# Inductive_displacement_sensor.net
KiCad netlist of a schematic drawn in EasyEDA Pro
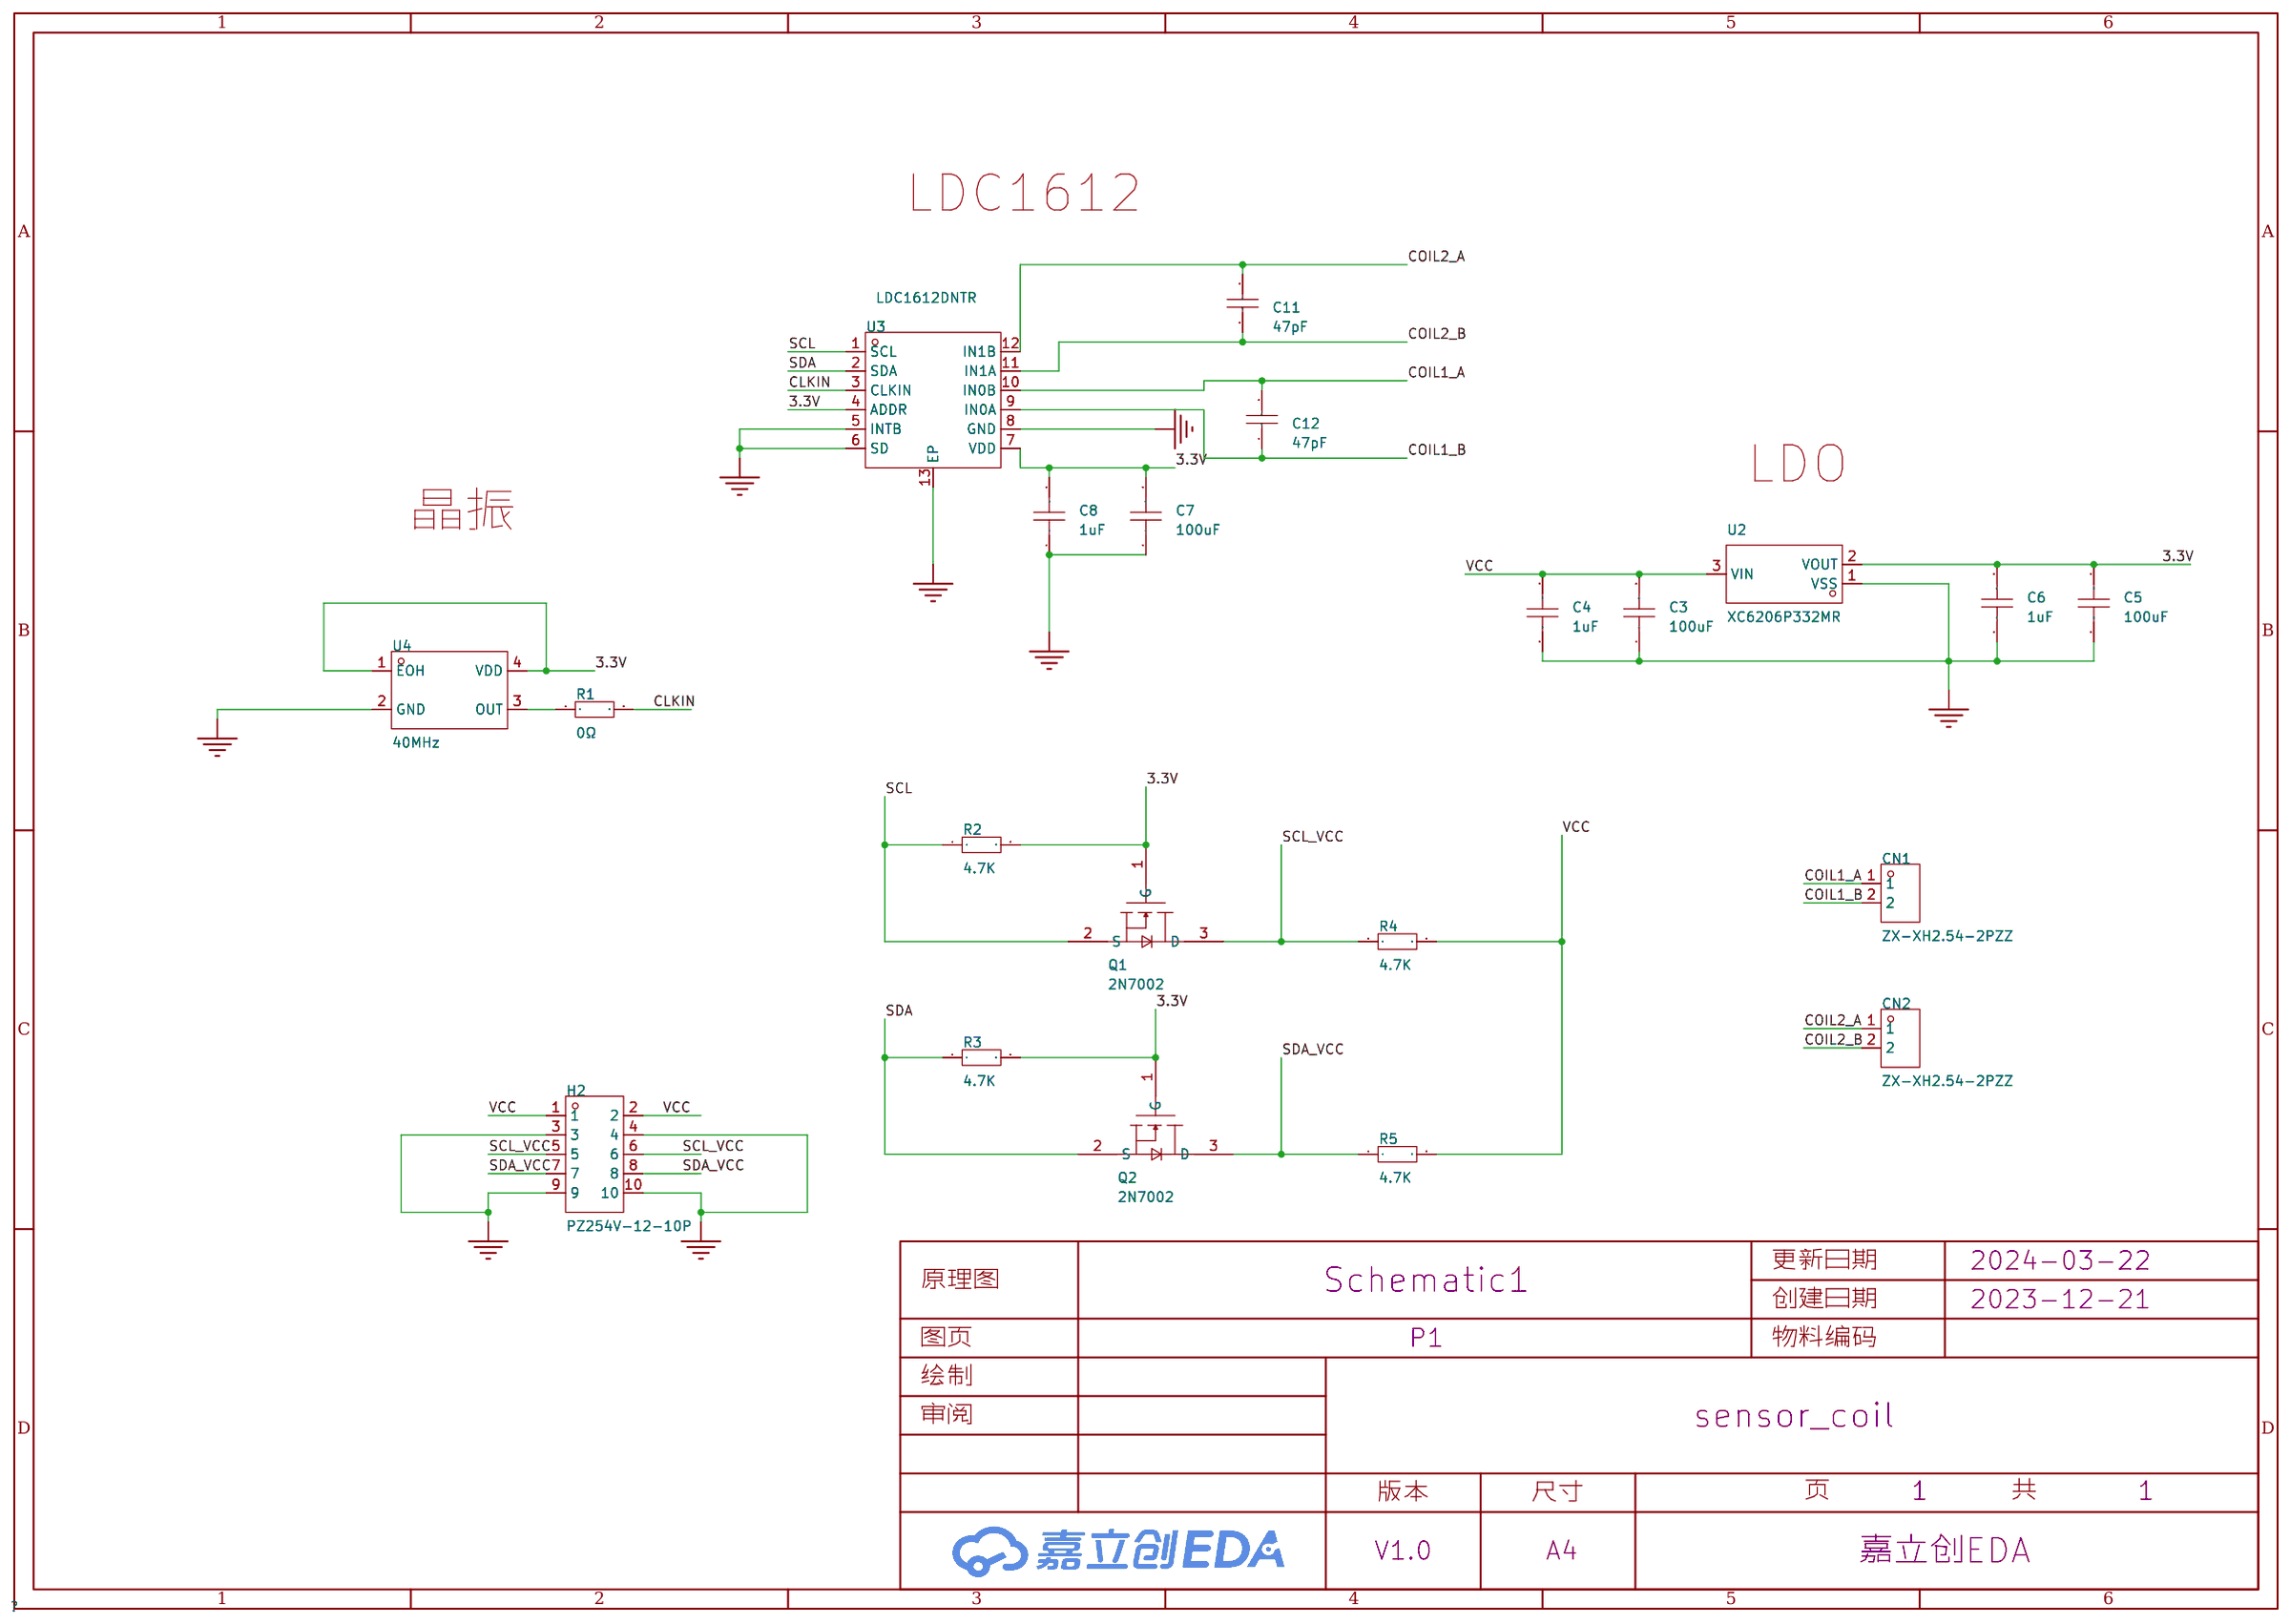
[diagram p0: schematic sheet]

(export (version "E")
  (design (tool "Eeschema 10.0.6"))
  (components
    (comp (ref "C3")
      (value "100uF")
      (footprint "easyedapro:C0603")
      (libsource (lib "easyedapro") (part "CapAcitance"))
    )
    (comp (ref "C4")
      (value "1uF")
      (footprint "easyedapro:C0603")
      (libsource (lib "easyedapro") (part "CapAcitance"))
    )
    (comp (ref "C5")
      (value "100uF")
      (footprint "easyedapro:C0603")
      (libsource (lib "easyedapro") (part "CapAcitance"))
    )
    (comp (ref "C6")
      (value "1uF")
      (footprint "easyedapro:C0603")
      (libsource (lib "easyedapro") (part "CapAcitance"))
    )
    (comp (ref "C7")
      (value "100uF")
      (footprint "easyedapro:C0603")
      (libsource (lib "easyedapro") (part "CapAcitance"))
    )
    (comp (ref "C8")
      (value "1uF")
      (footprint "easyedapro:C0603")
      (libsource (lib "easyedapro") (part "CapAcitance"))
    )
    (comp (ref "C11")
      (value "47pF")
      (footprint "easyedapro:C0402")
      (description "容值:47pF;精度:±5%;额定电压:50V;材质(温度系数):C0G;")
      (fields (field (name "Manufacturer Part") "0402CG470J500NT") (field (name "Manufacturer") "FH(风华)"))
      (libsource (lib "easyedapro") (part "0402CG470J500NT"))
    )
    (comp (ref "C12")
      (value "47pF")
      (footprint "easyedapro:C0402")
      (description "容值:47pF;精度:±5%;额定电压:50V;材质(温度系数):C0G;")
      (fields (field (name "Manufacturer Part") "0402CG470J500NT") (field (name "Manufacturer") "FH(风华)"))
      (libsource (lib "easyedapro") (part "0402CG470J500NT"))
    )
    (comp (ref "CN1")
      (value "ZX-XH2.54-2PZZ")
      (footprint "easyedapro:CONN-TH_2P-P2.50_HX25003-2A")
      (fields (field (name "Manufacturer") "Megastar(兆星)"))
      (libsource (lib "easyedapro") (part "ZX-XH2.54-2PZZ"))
    )
    (comp (ref "CN2")
      (value "ZX-XH2.54-2PZZ")
      (footprint "easyedapro:CONN-TH_2P-P2.50_HX25003-2A")
      (fields (field (name "Manufacturer") "Megastar(兆星)"))
      (libsource (lib "easyedapro") (part "ZX-XH2.54-2PZZ"))
    )
    (comp (ref "H2")
      (value "PZ254V-12-10P")
      (footprint "easyedapro:HDR-TH_10P-P2.54-V-M-R2-C5-S2.54")
      (fields (field (name "Manufacturer") "XFCN(兴飞)"))
      (libsource (lib "easyedapro") (part "PZ254V-12-10P"))
    )
    (comp (ref "Q1")
      (value "2N7002")
      (footprint "easyedapro:SOT-23-3_L2.9-W1.3-P1.90-LS2.4-BR")
      (fields (field (name "Manufacturer") "JSMSEMI(杰盛微)"))
      (libsource (lib "easyedapro") (part "2N7002_C916396"))
    )
    (comp (ref "Q2")
      (value "2N7002")
      (footprint "easyedapro:SOT-23-3_L2.9-W1.3-P1.90-LS2.4-BR")
      (fields (field (name "Manufacturer") "JSMSEMI(杰盛微)"))
      (libsource (lib "easyedapro") (part "2N7002_C916396"))
    )
    (comp (ref "R1") (value "0Ω") (footprint "easyedapro:R0603") (libsource (lib "easyedapro") (part "电阻")))
    (comp (ref "R2") (value "4.7K") (footprint "easyedapro:R0603") (libsource (lib "easyedapro") (part "电阻")))
    (comp (ref "R3") (value "4.7K") (footprint "easyedapro:R0603") (libsource (lib "easyedapro") (part "电阻")))
    (comp (ref "R4") (value "4.7K") (footprint "easyedapro:R0603") (libsource (lib "easyedapro") (part "电阻")))
    (comp (ref "R5") (value "4.7K") (footprint "easyedapro:R0603") (libsource (lib "easyedapro") (part "电阻")))
    (comp (ref "U2")
      (value "XC6206P332MR")
      (footprint "easyedapro:SOT-23-3_L3.0-W1.7-P0.95-LS2.9-BR")
      (description "输出类型:固定;最大输入电压:8V;输出电压:3.3V;最大输出电流:250mA;电源纹波抑制比(PSRR):40dB@(1kHz);输出极性:正极;")
      (fields (field (name "Manufacturer") "UMW(友台半导体)"))
      (libsource (lib "easyedapro") (part "XC6206P332MR_C347376"))
    )
    (comp (ref "U3")
      (value "LDC1612DNTR")
      (footprint "easyedapro:WSON-12_L4.0-W4.0-P0.50-BL-EP")
      (description "LDC1612 2 通道、28 位、高分辨率电感数字转换器")
      (fields (field (name "Manufacturer") "TI(德州仪器)"))
      (libsource (lib "easyedapro") (part "LDC1612DNTR"))
    )
    (comp (ref "U4")
      (value "40MHz")
      (footprint "easyedapro:OSC-SMD_4P-L2.5-W2.0-BL")
      (description "频率:40MHz;输出模式:CMOS;工作电压:3.3V;供电电流:15mA;频率稳定度(全温):±50ppm;")
      (fields (field (name "Manufacturer Part") "625L3C040M00000") (field (name "Manufacturer") "CTS(西迪斯)"))
      (libsource (lib "easyedapro") (part "625L3C040M00000"))
    )
  )
  (nets
    (net (code "1") (name "/3.3V") (class "Default")
      (node (ref "C5") (pin "2") (pinfunction "2_2") (pintype "input"))
      (node (ref "C6") (pin "2") (pinfunction "2_2") (pintype "input"))
      (node (ref "C7") (pin "2") (pinfunction "2_2") (pintype "input"))
      (node (ref "C8") (pin "2") (pinfunction "2_2") (pintype "input"))
      (node (ref "Q1") (pin "1") (pinfunction "G_1") (pintype "unspecified"))
      (node (ref "Q2") (pin "1") (pinfunction "G_1") (pintype "unspecified"))
      (node (ref "R2") (pin "2") (pinfunction "2_2") (pintype "input"))
      (node (ref "R3") (pin "2") (pinfunction "2_2") (pintype "input"))
      (node (ref "U2") (pin "2") (pinfunction "VOUT_2") (pintype "unspecified"))
      (node (ref "U3") (pin "4") (pinfunction "ADDR_4") (pintype "unspecified"))
      (node (ref "U3") (pin "7") (pinfunction "VDD_7") (pintype "unspecified"))
      (node (ref "U4") (pin "1") (pinfunction "EOH_1") (pintype "unspecified"))
      (node (ref "U4") (pin "4") (pinfunction "VDD_4") (pintype "unspecified"))
    )
    (net (code "2") (name "/CLKIN") (class "Default")
      (node (ref "R1") (pin "2") (pinfunction "2_2") (pintype "input"))
      (node (ref "U3") (pin "3") (pinfunction "CLKIN_3") (pintype "unspecified"))
    )
    (net (code "3") (name "/COIL1_A") (class "Default")
      (node (ref "C12") (pin "2") (pinfunction "2_2") (pintype "input"))
      (node (ref "CN1") (pin "1") (pinfunction "1_1") (pintype "unspecified"))
      (node (ref "U3") (pin "10") (pinfunction "IN0B_10") (pintype "unspecified"))
    )
    (net (code "4") (name "/COIL1_B") (class "Default")
      (node (ref "C12") (pin "1") (pinfunction "1_1") (pintype "input"))
      (node (ref "CN1") (pin "2") (pinfunction "2_2") (pintype "unspecified"))
      (node (ref "U3") (pin "9") (pinfunction "IN0A_9") (pintype "unspecified"))
    )
    (net (code "5") (name "/COIL2_A") (class "Default")
      (node (ref "C11") (pin "2") (pinfunction "2_2") (pintype "input"))
      (node (ref "CN2") (pin "1") (pinfunction "1_1") (pintype "unspecified"))
      (node (ref "U3") (pin "12") (pinfunction "IN1B_12") (pintype "unspecified"))
    )
    (net (code "6") (name "/COIL2_B") (class "Default")
      (node (ref "C11") (pin "1") (pinfunction "1_1") (pintype "input"))
      (node (ref "CN2") (pin "2") (pinfunction "2_2") (pintype "unspecified"))
      (node (ref "U3") (pin "11") (pinfunction "IN1A_11") (pintype "unspecified"))
    )
    (net (code "7") (name "/SCL") (class "Default")
      (node (ref "Q1") (pin "2") (pinfunction "S_2") (pintype "unspecified"))
      (node (ref "R2") (pin "1") (pinfunction "1_1") (pintype "input"))
      (node (ref "U3") (pin "1") (pinfunction "SCL_1") (pintype "unspecified"))
    )
    (net (code "8") (name "/SCL_VCC") (class "Default")
      (node (ref "H2") (pin "5") (pinfunction "5_5") (pintype "unspecified"))
      (node (ref "H2") (pin "6") (pinfunction "6_6") (pintype "unspecified"))
      (node (ref "Q1") (pin "3") (pinfunction "D_3") (pintype "unspecified"))
      (node (ref "R4") (pin "1") (pinfunction "1_1") (pintype "input"))
    )
    (net (code "9") (name "/SDA") (class "Default")
      (node (ref "Q2") (pin "2") (pinfunction "S_2") (pintype "unspecified"))
      (node (ref "R3") (pin "1") (pinfunction "1_1") (pintype "input"))
      (node (ref "U3") (pin "2") (pinfunction "SDA_2") (pintype "unspecified"))
    )
    (net (code "10") (name "/SDA_VCC") (class "Default")
      (node (ref "H2") (pin "7") (pinfunction "7_7") (pintype "unspecified"))
      (node (ref "H2") (pin "8") (pinfunction "8_8") (pintype "unspecified"))
      (node (ref "Q2") (pin "3") (pinfunction "D_3") (pintype "unspecified"))
      (node (ref "R5") (pin "1") (pinfunction "1_1") (pintype "input"))
    )
    (net (code "11") (name "/VCC") (class "Default")
      (node (ref "C3") (pin "2") (pinfunction "2_2") (pintype "input"))
      (node (ref "C4") (pin "2") (pinfunction "2_2") (pintype "input"))
      (node (ref "H2") (pin "1") (pinfunction "1_1") (pintype "unspecified"))
      (node (ref "H2") (pin "2") (pinfunction "2_2") (pintype "unspecified"))
      (node (ref "R4") (pin "2") (pinfunction "2_2") (pintype "input"))
      (node (ref "R5") (pin "2") (pinfunction "2_2") (pintype "input"))
      (node (ref "U2") (pin "3") (pinfunction "VIN_3") (pintype "unspecified"))
    )
    (net (code "12") (name "GND") (class "Default")
      (node (ref "C3") (pin "1") (pinfunction "1_1") (pintype "input"))
      (node (ref "C4") (pin "1") (pinfunction "1_1") (pintype "input"))
      (node (ref "C5") (pin "1") (pinfunction "1_1") (pintype "input"))
      (node (ref "C6") (pin "1") (pinfunction "1_1") (pintype "input"))
      (node (ref "C7") (pin "1") (pinfunction "1_1") (pintype "input"))
      (node (ref "C8") (pin "1") (pinfunction "1_1") (pintype "input"))
      (node (ref "H2") (pin "10") (pinfunction "10_10") (pintype "unspecified"))
      (node (ref "H2") (pin "3") (pinfunction "3_3") (pintype "unspecified"))
      (node (ref "H2") (pin "4") (pinfunction "4_4") (pintype "unspecified"))
      (node (ref "H2") (pin "9") (pinfunction "9_9") (pintype "unspecified"))
      (node (ref "U2") (pin "1") (pinfunction "VSS_1") (pintype "unspecified"))
      (node (ref "U3") (pin "13") (pinfunction "EP_13") (pintype "unspecified"))
      (node (ref "U3") (pin "5") (pinfunction "INTB_5") (pintype "unspecified"))
      (node (ref "U3") (pin "6") (pinfunction "SD_6") (pintype "unspecified"))
      (node (ref "U3") (pin "8") (pinfunction "GND_8") (pintype "unspecified"))
      (node (ref "U4") (pin "2") (pinfunction "GND_2") (pintype "unspecified"))
    )
    (net (code "13") (name "Net-(U4-OUT)") (class "Default")
      (node (ref "R1") (pin "1") (pinfunction "1_1") (pintype "input"))
      (node (ref "U4") (pin "3") (pinfunction "OUT_3") (pintype "unspecified"))
    )
  )
)
